# M4F_MCU_Power.net
KiCad netlist of a schematic drawn in Altium Designer
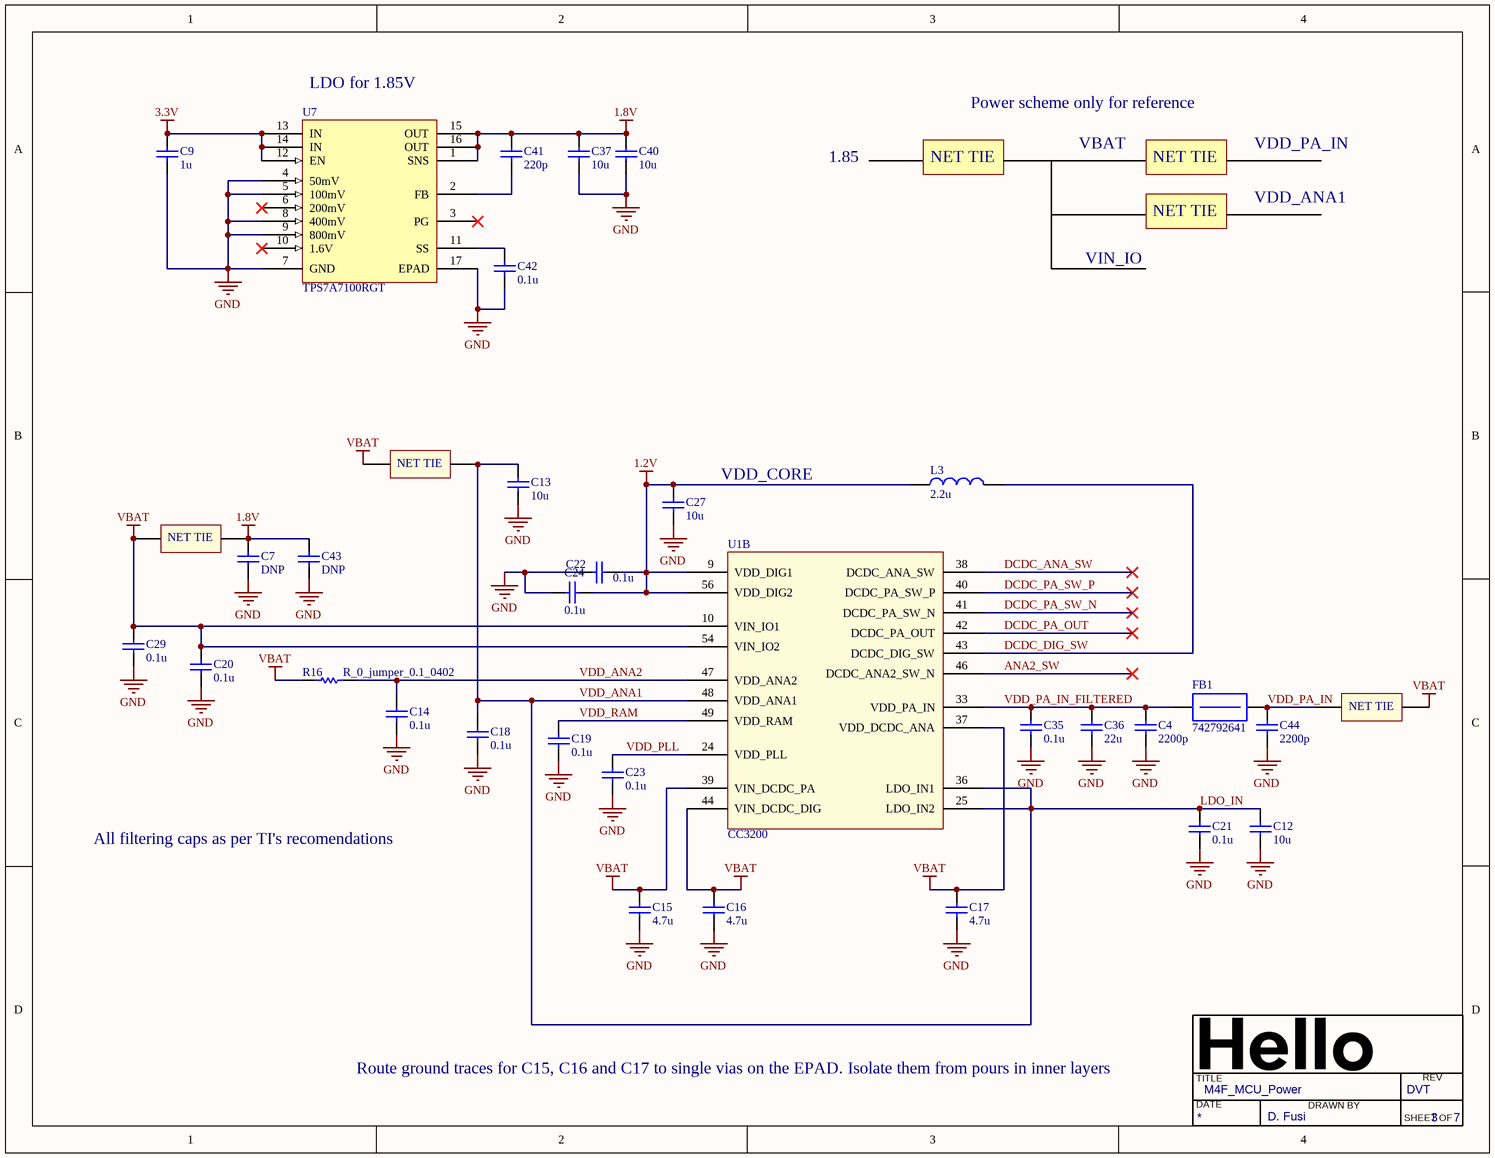
[diagram p0: M4F_MCU_Power.SchDoc]

(export (version "E")
  (design (tool "Eeschema 10.0.6"))
  (components
    (comp (ref "C4")
      (value "2200p")
      (footprint "CAP0402_SENSE_DVT")
      (description "Chip capacitor")
      (fields (field (name "TOLERANCE") "5 %") (field (name "VOLTAGE") "16V"))
      (libsource (lib "Morpheus_pill") (part "C_2200p_5_16_STD_0402"))
    )
    (comp (ref "C7")
      (value "DNP")
      (footprint "CAP1206_SENSE_DVT")
      (description "Chip capacitor")
      (fields (field (name "TOLERANCE") "20%") (field (name "VOLTAGE") "6.3V"))
      (libsource (lib "Morpheus_pill") (part "C_100u_20_6.3_X5R_1206"))
    )
    (comp (ref "C9")
      (value "1u")
      (footprint "CAP0603_SENSE_DVT")
      (description "Chip capacitor")
      (fields (field (name "TOLERANCE") "10%") (field (name "VOLTAGE") "16V"))
      (libsource (lib "Morpheus_pill") (part "C_1u_10_16_X5R_0603"))
    )
    (comp (ref "C12")
      (value "10u")
      (footprint "CAP0603_SENSE_DVT")
      (description "Chip capacitor")
      (fields (field (name "TOLERANCE") "10%") (field (name "VOLTAGE") "6.3V"))
      (libsource (lib "Morpheus_pill") (part "C_10u_10_6.3_X5R_0603"))
    )
    (comp (ref "C13")
      (value "10u")
      (footprint "CAP0603_SENSE_DVT")
      (description "Chip capacitor")
      (fields (field (name "TOLERANCE") "10%") (field (name "VOLTAGE") "6.3V"))
      (libsource (lib "Morpheus_pill") (part "C_10u_10_6.3_X5R_0603"))
    )
    (comp (ref "C14")
      (value "0.1u")
      (footprint "CAP0603_SENSE_DVT")
      (description "Chip capacitor")
      (fields (field (name "TOLERANCE") "20%") (field (name "VOLTAGE") "16V"))
      (libsource (lib "Morpheus_pill") (part "C_0.1u_20_16_X7R_0603"))
    )
    (comp (ref "C15")
      (value "4.7u")
      (footprint "CAP0603_SENSE_DVT")
      (description "Chip capacitor")
      (fields (field (name "TOLERANCE") "20%") (field (name "VOLTAGE") "10V"))
      (libsource (lib "Morpheus_pill") (part "C_4.7u_20_10_X5R_0603"))
    )
    (comp (ref "C16")
      (value "4.7u")
      (footprint "CAP0603_SENSE_DVT")
      (description "Chip capacitor")
      (fields (field (name "TOLERANCE") "20%") (field (name "VOLTAGE") "10V"))
      (libsource (lib "Morpheus_pill") (part "C_4.7u_20_10_X5R_0603"))
    )
    (comp (ref "C17")
      (value "4.7u")
      (footprint "CAP0603_SENSE_DVT")
      (description "Chip capacitor")
      (fields (field (name "TOLERANCE") "20%") (field (name "VOLTAGE") "10V"))
      (libsource (lib "Morpheus_pill") (part "C_4.7u_20_10_X5R_0603"))
    )
    (comp (ref "C18")
      (value "0.1u")
      (footprint "CAP0603_SENSE_DVT")
      (description "Chip capacitor")
      (fields (field (name "TOLERANCE") "20%") (field (name "VOLTAGE") "16V"))
      (libsource (lib "Morpheus_pill") (part "C_0.1u_20_16_X7R_0603"))
    )
    (comp (ref "C19")
      (value "0.1u")
      (footprint "CAP0603_SENSE_DVT")
      (description "Chip capacitor")
      (fields (field (name "TOLERANCE") "20%") (field (name "VOLTAGE") "16V"))
      (libsource (lib "Morpheus_pill") (part "C_0.1u_20_16_X7R_0603"))
    )
    (comp (ref "C20")
      (value "0.1u")
      (footprint "CAP0603_SENSE_DVT")
      (description "Chip capacitor")
      (fields (field (name "TOLERANCE") "20%") (field (name "VOLTAGE") "16V"))
      (libsource (lib "Morpheus_pill") (part "C_0.1u_20_16_X7R_0603"))
    )
    (comp (ref "C21")
      (value "0.1u")
      (footprint "CAP0603_SENSE_DVT")
      (description "Chip capacitor")
      (fields (field (name "TOLERANCE") "20%") (field (name "VOLTAGE") "16V"))
      (libsource (lib "Morpheus_pill") (part "C_0.1u_20_16_X7R_0603"))
    )
    (comp (ref "C22")
      (value "0.1u")
      (footprint "CAP0603_SENSE_DVT")
      (description "Chip capacitor")
      (fields (field (name "TOLERANCE") "20%") (field (name "VOLTAGE") "16V"))
      (libsource (lib "Morpheus_pill") (part "C_0.1u_20_16_X7R_0603"))
    )
    (comp (ref "C23")
      (value "0.1u")
      (footprint "CAP0603_SENSE_DVT")
      (description "Chip capacitor")
      (fields (field (name "TOLERANCE") "20%") (field (name "VOLTAGE") "16V"))
      (libsource (lib "Morpheus_pill") (part "C_0.1u_20_16_X7R_0603"))
    )
    (comp (ref "C24")
      (value "0.1u")
      (footprint "CAP0603_SENSE_DVT")
      (description "Chip capacitor")
      (fields (field (name "TOLERANCE") "20%") (field (name "VOLTAGE") "16V"))
      (libsource (lib "Morpheus_pill") (part "C_0.1u_20_16_X7R_0603"))
    )
    (comp (ref "C27")
      (value "10u")
      (footprint "CAP0603_SENSE_DVT")
      (description "Chip capacitor")
      (fields (field (name "TOLERANCE") "10%") (field (name "VOLTAGE") "6.3V"))
      (libsource (lib "Morpheus_pill") (part "C_10u_10_6.3_X5R_0603"))
    )
    (comp (ref "C29")
      (value "0.1u")
      (footprint "CAP0603_SENSE_DVT")
      (description "Chip capacitor")
      (fields (field (name "TOLERANCE") "20%") (field (name "VOLTAGE") "16V"))
      (libsource (lib "Morpheus_pill") (part "C_0.1u_20_16_X7R_0603"))
    )
    (comp (ref "C35")
      (value "0.1u")
      (footprint "CAP0603_SENSE_DVT")
      (description "Chip capacitor")
      (fields (field (name "TOLERANCE") "20%") (field (name "VOLTAGE") "16V"))
      (libsource (lib "Morpheus_pill") (part "C_0.1u_20_16_X7R_0603"))
    )
    (comp (ref "C36")
      (value "22u")
      (footprint "CAP0603_SENSE_DVT")
      (description "Chip capacitor")
      (fields (field (name "TOLERANCE") "20%") (field (name "VOLTAGE") "10V"))
      (libsource (lib "Morpheus_pill") (part "C_22u_10_20_JB_0603"))
    )
    (comp (ref "C37")
      (value "10u")
      (footprint "CAP0805_SENSE_DVT")
      (description "Chip capacitor")
      (fields (field (name "TOLERANCE") "20%") (field (name "VOLTAGE") "10V"))
      (libsource (lib "Morpheus_pill") (part "C_10u_20_10_X7R_0805"))
    )
    (comp (ref "C40")
      (value "10u")
      (footprint "CAP0805_SENSE_DVT")
      (description "Chip capacitor")
      (fields (field (name "TOLERANCE") "20%") (field (name "VOLTAGE") "10V"))
      (libsource (lib "Morpheus_pill") (part "C_10u_20_10_X7R_0805"))
    )
    (comp (ref "C41")
      (value "220p")
      (footprint "CAP0402_SENSE_DVT")
      (description "Chip capacitor")
      (fields (field (name "TOLERANCE") "5%") (field (name "VOLTAGE") "50V"))
      (libsource (lib "Morpheus_pill") (part "C_220p_5_50_NP0_0402"))
    )
    (comp (ref "C42")
      (value "0.1u")
      (footprint "CAP0603_SENSE_DVT")
      (description "Chip capacitor")
      (fields (field (name "TOLERANCE") "20%") (field (name "VOLTAGE") "16V"))
      (libsource (lib "Morpheus_pill") (part "C_0.1u_20_16_X7R_0603"))
    )
    (comp (ref "C43")
      (value "DNP")
      (footprint "CAP1206_SENSE_DVT")
      (description "Chip capacitor")
      (fields (field (name "TOLERANCE") "20%") (field (name "VOLTAGE") "6.3V"))
      (libsource (lib "Morpheus_pill") (part "C_100u_20_6.3_X5R_1206"))
    )
    (comp (ref "C44")
      (value "2200p")
      (footprint "CAP0402_SENSE_DVT")
      (description "Chip capacitor")
      (fields (field (name "TOLERANCE") "5 %") (field (name "VOLTAGE") "16V"))
      (libsource (lib "Morpheus_pill") (part "C_2200p_5_16_STD_0402"))
    )
    (comp (ref "FB1")
      (value "742792641")
      (footprint "RES0603_SENSE_DVT")
      (description "Ferrite bead, 300 ohm impedance")
      (libsource (lib "Morpheus_pill") (part "FB_300_2_0.15_0603"))
    )
    (comp (ref "L3")
      (value "2.2u")
      (footprint "IND_1008")
      (description "SMD power inductor, 2.2uH")
      (fields (field (name "TOLERANCE") "20%"))
      (libsource (lib "Morpheus_pill") (part "L_2.2u_20_?_0.08_?_1.3"))
    )
    (comp (ref "NT1")
      (value "NT")
      (footprint "Net_tie_50mil")
      (description "Net tie to bridge 50 mil spacing connector holes")
      (libsource (lib "Morpheus_pill") (part "Net tie_50mil"))
    )
    (comp (ref "NT2")
      (value "NT")
      (footprint "Net_tie_50mil")
      (description "Net tie to bridge 50 mil spacing connector holes")
      (libsource (lib "Morpheus_pill") (part "Net tie_50mil"))
    )
    (comp (ref "NT3")
      (value "NT")
      (footprint "Net_tie_50mil")
      (description "Net tie to bridge 50 mil spacing connector holes")
      (libsource (lib "Morpheus_pill") (part "Net tie_50mil"))
    )
    (comp (ref "R16")
      (value "R_0_jumper_0.1_0402")
      (footprint "RES0402-SENSE-DVT")
      (description "Chip Resistor")
      (fields (field (name "TOLERANCE") "Jumper") (field (name "POWER") "0.1 W"))
      (libsource (lib "Morpheus_pill") (part "R_0_jumper_0.1_0402"))
    )
    (comp (ref "U1")
      (value "CC3200")
      (footprint "QFN50P900X900X100_HS-65N")
      (description "TI Wi-FI module")
      (libsource (lib "Morpheus_pill") (part "CC3200"))
    )
    (comp (ref "U7")
      (value "TPS7A7100RGT")
      (footprint "QFN50P300X300X100_HS-17N")
      (description "1A fast-transient LDO")
      (libsource (lib "Morpheus_pill") (part "TPS7A7100RGT"))
    )
  )
  (nets
    (net (code "1") (name "/ANA2_SW") (class "Default")
      (node (ref "U1") (pin "46") (pinfunction "DCDC_ANA2_SW_N_46") (pintype "power_in+no_connect"))
    )
    (net (code "2") (name "/DCDC_ANA_SW") (class "Default")
      (node (ref "U1") (pin "38") (pinfunction "DCDC_ANA_SW_38") (pintype "power_in+no_connect"))
    )
    (net (code "3") (name "/DCDC_DIG_SW") (class "Default")
      (node (ref "L3") (pin "2") (pintype "passive"))
      (node (ref "U1") (pin "43") (pinfunction "DCDC_DIG_SW_43") (pintype "power_in"))
    )
    (net (code "4") (name "/DCDC_PA_OUT") (class "Default")
      (node (ref "U1") (pin "42") (pinfunction "DCDC_PA_OUT_42") (pintype "power_in+no_connect"))
    )
    (net (code "5") (name "/DCDC_PA_SW_N") (class "Default")
      (node (ref "U1") (pin "41") (pinfunction "DCDC_PA_SW_N_41") (pintype "power_in+no_connect"))
    )
    (net (code "6") (name "/DCDC_PA_SW_P") (class "Default")
      (node (ref "U1") (pin "40") (pinfunction "DCDC_PA_SW_P_40") (pintype "power_in+no_connect"))
    )
    (net (code "7") (name "/LDO_IN") (class "Default")
      (node (ref "C12") (pin "2") (pinfunction "2_2") (pintype "passive"))
      (node (ref "C13") (pin "2") (pinfunction "2_2") (pintype "passive"))
      (node (ref "C18") (pin "2") (pinfunction "2_2") (pintype "passive"))
      (node (ref "C21") (pin "2") (pinfunction "2_2") (pintype "passive"))
      (node (ref "NT1") (pin "2") (pinfunction "2_2") (pintype "passive"))
      (node (ref "U1") (pin "25") (pinfunction "LDO_IN2_25") (pintype "power_in"))
      (node (ref "U1") (pin "36") (pinfunction "LDO_IN1_36") (pintype "power_in"))
      (node (ref "U1") (pin "48") (pinfunction "VDD_ANA1_48") (pintype "power_in"))
    )
    (net (code "8") (name "/VDD_ANA2") (class "Default")
      (node (ref "C14") (pin "2") (pinfunction "2_2") (pintype "passive"))
      (node (ref "R16") (pin "2") (pinfunction "2_2") (pintype "passive"))
      (node (ref "U1") (pin "47") (pinfunction "VDD_ANA2_47") (pintype "power_in"))
    )
    (net (code "9") (name "/VDD_PA_IN") (class "Default")
      (node (ref "C44") (pin "2") (pinfunction "2_2") (pintype "passive"))
      (node (ref "FB1") (pin "2") (pintype "passive"))
      (node (ref "NT3") (pin "1") (pinfunction "1_1") (pintype "passive"))
    )
    (net (code "10") (name "/VDD_PA_IN_FILTERED") (class "Default")
      (node (ref "C35") (pin "2") (pinfunction "2_2") (pintype "passive"))
      (node (ref "C36") (pin "2") (pinfunction "2_2") (pintype "passive"))
      (node (ref "C4") (pin "2") (pinfunction "2_2") (pintype "passive"))
      (node (ref "FB1") (pin "1") (pintype "passive"))
      (node (ref "U1") (pin "33") (pinfunction "VDD_PA_IN_33") (pintype "power_in"))
    )
    (net (code "11") (name "/VDD_PLL") (class "Default")
      (node (ref "C23") (pin "2") (pinfunction "2_2") (pintype "passive"))
      (node (ref "U1") (pin "24") (pinfunction "VDD_PLL_24") (pintype "power_in"))
    )
    (net (code "12") (name "/VDD_RAM") (class "Default")
      (node (ref "C19") (pin "2") (pinfunction "2_2") (pintype "passive"))
      (node (ref "U1") (pin "49") (pinfunction "VDD_RAM_49") (pintype "power_in"))
    )
    (net (code "13") (name "1.2V") (class "Default")
      (node (ref "C22") (pin "2") (pinfunction "2_2") (pintype "passive"))
      (node (ref "C24") (pin "1") (pinfunction "1_1") (pintype "passive"))
      (node (ref "C27") (pin "2") (pinfunction "2_2") (pintype "passive"))
      (node (ref "L3") (pin "1") (pintype "passive"))
      (node (ref "U1") (pin "56") (pinfunction "VDD_DIG2_56") (pintype "power_in"))
      (node (ref "U1") (pin "9") (pinfunction "VDD_DIG1_9") (pintype "power_in"))
    )
    (net (code "14") (name "1.8V") (class "Default")
      (node (ref "C37") (pin "2") (pinfunction "2_2") (pintype "passive"))
      (node (ref "C40") (pin "2") (pinfunction "2_2") (pintype "passive"))
      (node (ref "C41") (pin "2") (pinfunction "2_2") (pintype "passive"))
      (node (ref "C43") (pin "2") (pinfunction "2_2") (pintype "passive"))
      (node (ref "C7") (pin "2") (pinfunction "2_2") (pintype "passive"))
      (node (ref "NT2") (pin "2") (pinfunction "2_2") (pintype "passive"))
      (node (ref "U7") (pin "1") (pinfunction "SNS_1") (pintype "passive"))
      (node (ref "U7") (pin "15") (pinfunction "OUT_15") (pintype "power_in"))
      (node (ref "U7") (pin "16") (pinfunction "OUT_16") (pintype "power_in"))
    )
    (net (code "15") (name "3.3V") (class "Default")
      (node (ref "C9") (pin "2") (pinfunction "2_2") (pintype "passive"))
      (node (ref "U7") (pin "12") (pinfunction "EN_12") (pintype "input"))
      (node (ref "U7") (pin "13") (pinfunction "IN_13") (pintype "power_in"))
      (node (ref "U7") (pin "14") (pinfunction "IN_14") (pintype "power_in"))
    )
    (net (code "16") (name "GND") (class "Default")
      (node (ref "C12") (pin "1") (pinfunction "1_1") (pintype "passive"))
      (node (ref "C13") (pin "1") (pinfunction "1_1") (pintype "passive"))
      (node (ref "C14") (pin "1") (pinfunction "1_1") (pintype "passive"))
      (node (ref "C15") (pin "1") (pinfunction "1_1") (pintype "passive"))
      (node (ref "C16") (pin "1") (pinfunction "1_1") (pintype "passive"))
      (node (ref "C17") (pin "1") (pinfunction "1_1") (pintype "passive"))
      (node (ref "C18") (pin "1") (pinfunction "1_1") (pintype "passive"))
      (node (ref "C19") (pin "1") (pinfunction "1_1") (pintype "passive"))
      (node (ref "C20") (pin "1") (pinfunction "1_1") (pintype "passive"))
      (node (ref "C21") (pin "1") (pinfunction "1_1") (pintype "passive"))
      (node (ref "C22") (pin "1") (pinfunction "1_1") (pintype "passive"))
      (node (ref "C23") (pin "1") (pinfunction "1_1") (pintype "passive"))
      (node (ref "C24") (pin "2") (pinfunction "2_2") (pintype "passive"))
      (node (ref "C27") (pin "1") (pinfunction "1_1") (pintype "passive"))
      (node (ref "C29") (pin "1") (pinfunction "1_1") (pintype "passive"))
      (node (ref "C35") (pin "1") (pinfunction "1_1") (pintype "passive"))
      (node (ref "C36") (pin "1") (pinfunction "1_1") (pintype "passive"))
      (node (ref "C37") (pin "1") (pinfunction "1_1") (pintype "passive"))
      (node (ref "C4") (pin "1") (pinfunction "1_1") (pintype "passive"))
      (node (ref "C40") (pin "1") (pinfunction "1_1") (pintype "passive"))
      (node (ref "C42") (pin "1") (pinfunction "1_1") (pintype "passive"))
      (node (ref "C43") (pin "1") (pinfunction "1_1") (pintype "passive"))
      (node (ref "C44") (pin "1") (pinfunction "1_1") (pintype "passive"))
      (node (ref "C7") (pin "1") (pinfunction "1_1") (pintype "passive"))
      (node (ref "C9") (pin "1") (pinfunction "1_1") (pintype "passive"))
      (node (ref "U7") (pin "17") (pinfunction "EPAD_17") (pintype "power_in"))
      (node (ref "U7") (pin "4") (pinfunction "50mV_4") (pintype "input"))
      (node (ref "U7") (pin "5") (pinfunction "100mV_5") (pintype "input"))
      (node (ref "U7") (pin "7") (pinfunction "GND_7") (pintype "power_in"))
      (node (ref "U7") (pin "8") (pinfunction "400mV_8") (pintype "input"))
      (node (ref "U7") (pin "9") (pinfunction "800mV_9") (pintype "input"))
    )
    (net (code "17") (name "Net-(U7-FB)") (class "Default")
      (node (ref "C41") (pin "1") (pinfunction "1_1") (pintype "passive"))
      (node (ref "U7") (pin "2") (pinfunction "FB_2") (pintype "passive"))
    )
    (net (code "18") (name "Net-(U7-SS)") (class "Default")
      (node (ref "C42") (pin "2") (pinfunction "2_2") (pintype "passive"))
      (node (ref "U7") (pin "11") (pinfunction "SS_11") (pintype "passive"))
    )
    (net (code "19") (name "VBAT") (class "Default")
      (node (ref "C15") (pin "2") (pinfunction "2_2") (pintype "passive"))
      (node (ref "C16") (pin "2") (pinfunction "2_2") (pintype "passive"))
      (node (ref "C17") (pin "2") (pinfunction "2_2") (pintype "passive"))
      (node (ref "C20") (pin "2") (pinfunction "2_2") (pintype "passive"))
      (node (ref "C29") (pin "2") (pinfunction "2_2") (pintype "passive"))
      (node (ref "NT1") (pin "1") (pinfunction "1_1") (pintype "passive"))
      (node (ref "NT2") (pin "1") (pinfunction "1_1") (pintype "passive"))
      (node (ref "NT3") (pin "2") (pinfunction "2_2") (pintype "passive"))
      (node (ref "R16") (pin "1") (pinfunction "1_1") (pintype "passive"))
      (node (ref "U1") (pin "10") (pinfunction "VIN_IO1_10") (pintype "power_in"))
      (node (ref "U1") (pin "37") (pinfunction "VDD_DCDC_ANA_37") (pintype "power_in"))
      (node (ref "U1") (pin "39") (pinfunction "VIN_DCDC_PA_39") (pintype "power_in"))
      (node (ref "U1") (pin "44") (pinfunction "VIN_DCDC_DIG_44") (pintype "power_in"))
      (node (ref "U1") (pin "54") (pinfunction "VIN_IO2_54") (pintype "power_in"))
    )
    (net (code "20") (name "unconnected-(U7-1.6V-Pad10)") (class "Default")
      (node (ref "U7") (pin "10") (pinfunction "1.6V_10") (pintype "input+no_connect"))
    )
    (net (code "21") (name "unconnected-(U7-200mV-Pad6)") (class "Default")
      (node (ref "U7") (pin "6") (pinfunction "200mV_6") (pintype "input+no_connect"))
    )
    (net (code "22") (name "unconnected-(U7-PG-Pad3)") (class "Default")
      (node (ref "U7") (pin "3") (pinfunction "PG_3") (pintype "open_collector+no_connect"))
    )
  )
)
